# power.net
KiCad netlist of a schematic drawn in Altium Designer
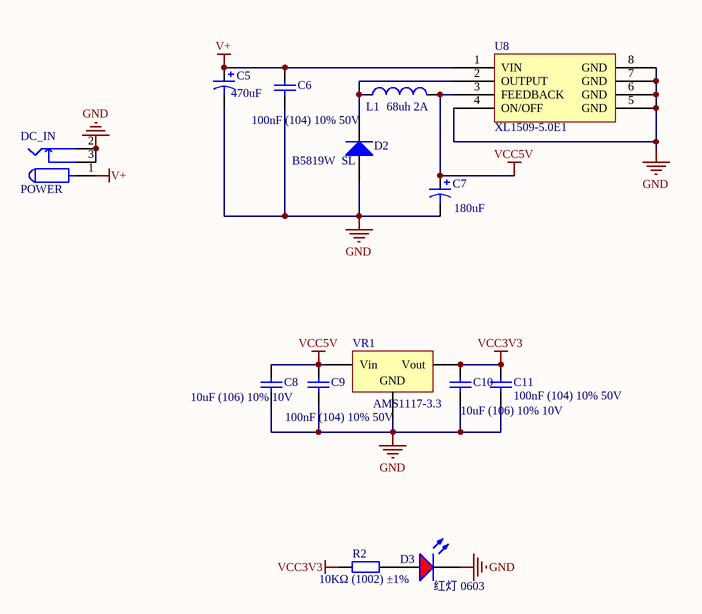
[diagram p0: power.SchDoc]

(export (version "E")
  (design (tool "Eeschema 10.0.6"))
  (components
    (comp (ref "C5")
      (value "470uF")
      (footprint "SMD-EC-F8")
      (description "Polarized Capacitor (Surface Mount)")
      (fields (field (name "Comment") "Cap Pol3") (field (name "PUBLISHER") "Altium Limited"))
      (libsource (lib "Miscellaneous Devices") (part "Cap Pol3"))
    )
    (comp (ref "C6")
      (value "100nF (104) 10% 50V")
      (footprint "0603_C")
      (description "贴片电容")
      (libsource (lib "Miscellaneous Devices LC") (part "0603 100nF (104) 10% 50V"))
    )
    (comp (ref "C7")
      (value "180uF")
      (footprint "470UF_A")
      (description "Polarized Capacitor (Surface Mount)")
      (fields (field (name "Comment") "Cap Pol3") (field (name "PUBLISHER") "Altium Limited"))
      (libsource (lib "Miscellaneous Devices") (part "Cap Pol3"))
    )
    (comp (ref "C8")
      (value "10uF (106) 10% 10V")
      (footprint "0603_C")
      (description "贴片电容")
      (libsource (lib "Miscellaneous Devices LC") (part "0603 10uF (106) 10% 10V"))
    )
    (comp (ref "C9")
      (value "100nF (104) 10% 50V")
      (footprint "0603_C")
      (description "贴片电容")
      (libsource (lib "Miscellaneous Devices LC") (part "0603 100nF (104) 10% 50V"))
    )
    (comp (ref "C10")
      (value "10uF (106) 10% 10V")
      (footprint "0603_C")
      (description "贴片电容")
      (libsource (lib "Miscellaneous Devices LC") (part "0603 10uF (106) 10% 10V"))
    )
    (comp (ref "C11")
      (value "100nF (104) 10% 50V")
      (footprint "0603_C")
      (description "贴片电容")
      (libsource (lib "Miscellaneous Devices LC") (part "0603 100nF (104) 10% 50V"))
    )
    (comp (ref "D2")
      (value "B5819W  SL")
      (footprint "SOD-123")
      (description "肖特基二极管")
      (libsource (lib "Miscellaneous Devices LC") (part "SOD-123 B5819W  SL"))
    )
    (comp (ref "D3")
      (value "红灯 0603")
      (footprint "0603_LED_S1")
      (description "发光二极管")
      (libsource (lib "Miscellaneous Devices LC") (part "0603 红灯"))
    )
    (comp (ref "DC_IN")
      (value "POWER")
      (footprint "DC10B")
      (libsource (lib "WarShip V3 STM32103封装库") (part "POW"))
    )
    (comp (ref "L1")
      (value "68uh 2A")
      (footprint "0630")
      (description "Inductor")
      (fields (field (name "PUBLISHER") "Altium Limited"))
      (libsource (lib "fd") (part "Inductor"))
    )
    (comp (ref "R2")
      (value "10KΩ (1002) ±1%")
      (footprint "0603_R")
      (description "贴片电阻")
      (libsource (lib "Miscellaneous Devices LC") (part "0603 10KΩ (1002) 1%"))
    )
    (comp (ref "U8")
      (value "XL1509-5.0E1")
      (footprint "SOP-8_150mil")
      (description "DC-DC芯片")
      (libsource (lib "Miscellaneous Devices LC") (part "XL1509-5.0E1_[C61063]"))
    )
    (comp (ref "VR1")
      (value "AMS1117-3.3")
      (footprint "SOT-223")
      (description "低压差线性稳压(LDO)")
      (libsource (lib "Miscellaneous Devices LC") (part "SOT-223 AMS1117-3.3"))
    )
  )
  (nets
    (net (code "1") (name "GND") (class "Default")
      (node (ref "C10") (pin "1") (pinfunction "1_1") (pintype "passive"))
      (node (ref "C11") (pin "1") (pinfunction "1_1") (pintype "passive"))
      (node (ref "C5") (pin "2") (pinfunction "2_2") (pintype "passive"))
      (node (ref "C6") (pin "1") (pinfunction "1_1") (pintype "passive"))
      (node (ref "C7") (pin "2") (pinfunction "2_2") (pintype "passive"))
      (node (ref "C8") (pin "1") (pinfunction "1_1") (pintype "passive"))
      (node (ref "C9") (pin "1") (pinfunction "1_1") (pintype "passive"))
      (node (ref "D2") (pin "1") (pinfunction "A_1") (pintype "passive"))
      (node (ref "D3") (pin "K") (pinfunction "K_K") (pintype "passive"))
      (node (ref "DC_IN") (pin "2") (pintype "passive"))
      (node (ref "DC_IN") (pin "3") (pintype "passive"))
      (node (ref "U8") (pin "4") (pinfunction "ON/OFF_4") (pintype "passive"))
      (node (ref "U8") (pin "5") (pinfunction "GND_5") (pintype "passive"))
      (node (ref "U8") (pin "6") (pinfunction "GND_6") (pintype "passive"))
      (node (ref "U8") (pin "7") (pinfunction "GND_7") (pintype "passive"))
      (node (ref "U8") (pin "8") (pinfunction "GND_8") (pintype "passive"))
      (node (ref "VR1") (pin "1") (pinfunction "GND_1") (pintype "passive"))
    )
    (net (code "2") (name "Net-(D2-K)") (class "Default")
      (node (ref "D2") (pin "2") (pinfunction "K_2") (pintype "passive"))
      (node (ref "L1") (pin "1") (pinfunction "1_1") (pintype "passive"))
      (node (ref "U8") (pin "2") (pinfunction "OUTPUT_2") (pintype "passive"))
    )
    (net (code "3") (name "Net-(D3-PadA)") (class "Default")
      (node (ref "D3") (pin "A") (pinfunction "A_A") (pintype "passive"))
      (node (ref "R2") (pin "2") (pinfunction "2_2") (pintype "passive"))
    )
    (net (code "4") (name "V+") (class "Default")
      (node (ref "C5") (pin "1") (pinfunction "1_1") (pintype "passive"))
      (node (ref "C6") (pin "2") (pinfunction "2_2") (pintype "passive"))
      (node (ref "DC_IN") (pin "1") (pintype "passive"))
      (node (ref "U8") (pin "1") (pinfunction "VIN_1") (pintype "passive"))
    )
    (net (code "5") (name "VCC3V3") (class "Default")
      (node (ref "C10") (pin "2") (pinfunction "2_2") (pintype "passive"))
      (node (ref "C11") (pin "2") (pinfunction "2_2") (pintype "passive"))
      (node (ref "R2") (pin "1") (pinfunction "1_1") (pintype "passive"))
      (node (ref "VR1") (pin "2") (pinfunction "Vout_2") (pintype "passive"))
    )
    (net (code "6") (name "VCC5V") (class "Default")
      (node (ref "C7") (pin "1") (pinfunction "1_1") (pintype "passive"))
      (node (ref "C8") (pin "2") (pinfunction "2_2") (pintype "passive"))
      (node (ref "C9") (pin "2") (pinfunction "2_2") (pintype "passive"))
      (node (ref "L1") (pin "2") (pinfunction "2_2") (pintype "passive"))
      (node (ref "U8") (pin "3") (pinfunction "FEEDBACK_3") (pintype "passive"))
      (node (ref "VR1") (pin "3") (pinfunction "Vin_3") (pintype "passive"))
    )
  )
)
